# Power_Supply.net
KiCad netlist of a schematic drawn in Altium Designer
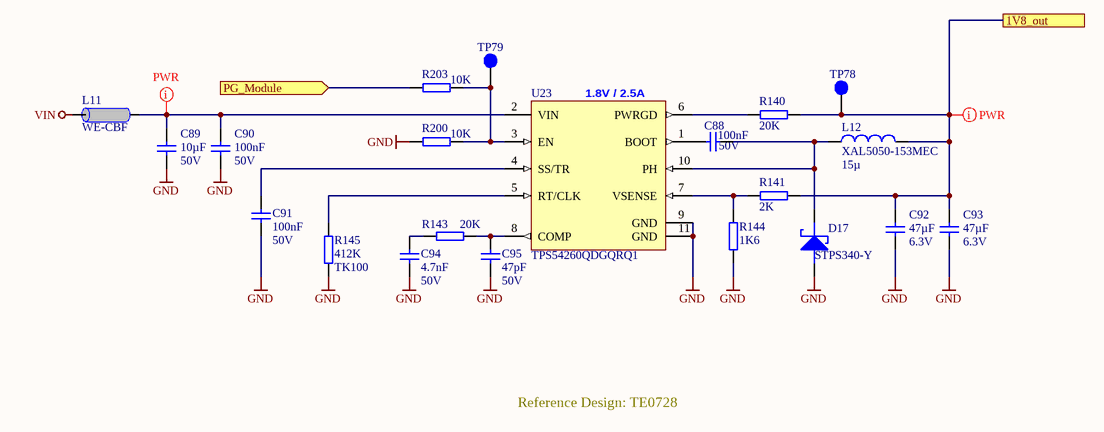
[diagram p0: Power_Supply.SchDoc]

(export (version "E")
  (design (tool "Eeschema 10.0.6"))
  (components
    (comp (ref "C88")
      (value "100nF")
      (footprint "CAPC1608X90N_FED")
      (description "KON 100nF 50V X7R ±10% SMD BF 1608 (0603)")
      (fields (field (name "TOLERANCE") "±10%") (field (name "VOLTAGE") "50V"))
      (libsource (lib "TE") (part "CAP-NP"))
    )
    (comp (ref "C89")
      (value "10µF")
      (footprint "CAPC3216X180N_V")
      (description "KON 10µF 50V X5R 10%  SMD BF 3216 (1206)")
      (fields (field (name "VOLTAGE") "50V") (field (name "TOLERANCE") "10%"))
      (libsource (lib "TE") (part "CAP-NP"))
    )
    (comp (ref "C90")
      (value "100nF")
      (footprint "CAPC1608X90N_FED")
      (description "KON 100nF 50V X7R ±10% SMD BF 1608 (0603)")
      (fields (field (name "TOLERANCE") "±10%") (field (name "VOLTAGE") "50V"))
      (libsource (lib "TE") (part "CAP-NP"))
    )
    (comp (ref "C91")
      (value "100nF")
      (footprint "CAPC1608X90N_FED")
      (description "KON 100nF 50V X7R ±10% SMD BF 1608 (0603)")
      (fields (field (name "TOLERANCE") "±10%") (field (name "VOLTAGE") "50V"))
      (libsource (lib "TE") (part "CAP-NP"))
    )
    (comp (ref "C92")
      (value "47µF")
      (footprint "CAPC2012X135N_V")
      (description "KON 47µF 6,3V X5R 20% SMD BF 2012 (0805)")
      (fields (field (name "TOLERANCE") "20%") (field (name "VOLTAGE") "6.3V"))
      (libsource (lib "TE") (part "CAP-NP"))
    )
    (comp (ref "C93")
      (value "47µF")
      (footprint "CAPC2012X135N_V")
      (description "KON 47µF 6,3V X5R 20% SMD BF 2012 (0805)")
      (fields (field (name "TOLERANCE") "20%") (field (name "VOLTAGE") "6.3V"))
      (libsource (lib "TE") (part "CAP-NP"))
    )
    (comp (ref "C94")
      (value "4.7nF")
      (footprint "CAPC1608X90N_FED")
      (description "KON 4.7nF 50V NP0 ±5%  SMD BF 1608 (0603)")
      (fields (field (name "TOLERANCE") "±5%") (field (name "VOLTAGE") "50V"))
      (libsource (lib "TE") (part "CAP-NP"))
    )
    (comp (ref "C95")
      (value "47pF")
      (footprint "CAPC1608X90N_FED")
      (description "KON 47pF 50V NP0 5%  SMD BF 1608 (0603)")
      (fields (field (name "TOLERANCE") "5%") (field (name "VOLTAGE") "50V"))
      (libsource (lib "TE") (part "CAP-NP"))
    )
    (comp (ref "D17")
      (value "STPS340-Y")
      (footprint "DIOM5336X265N")
      (description "STPS340-UY")
      (fields (field (name "VOLTAGE") "40V"))
      (libsource (lib "TE") (part "SCHOTTKY"))
    )
    (comp (ref "L11")
      (value "WE-CBF")
      (footprint "INDC2012X92N_V")
      (description "Ferritdurchführung SMD 0805")
      (fields (field (name "VOLTAGE") "2000mA"))
      (libsource (lib "TE") (part "Ferritperle"))
    )
    (comp (ref "L12")
      (value "XAL5050-153MEC")
      (footprint "IND_XAL5050")
      (description "Power Inductor 15µH 20% 3.9A 76.7mOhms")
      (fields (field (name "ALTIUM_VALUE") "15µ") (field (name "VOLTAGE") "3.9A 76.7mOhms"))
      (libsource (lib "TE") (part "IND"))
    )
    (comp (ref "R140")
      (value "20K")
      (footprint "RESC1608X55N_FED")
      (description "WID SMD 20K 1% 0,1W")
      (fields (field (name "TOLERANCE") "1%"))
      (libsource (lib "TE") (part "RES"))
    )
    (comp (ref "R141")
      (value "2K")
      (footprint "RESC1608X55N_FED")
      (description "WID SMD 2K 1% 0,1W AEC-Q200")
      (fields (field (name "TOLERANCE") "1%"))
      (libsource (lib "TE") (part "RES"))
    )
    (comp (ref "R143")
      (value "20K")
      (footprint "RESC1608X55N_FED")
      (description "WID SMD 20K 1% 0,1W")
      (fields (field (name "TOLERANCE") "1%"))
      (libsource (lib "TE") (part "RES"))
    )
    (comp (ref "R144")
      (value "1K6")
      (footprint "RESC1608X55N_FED")
      (description "WID SMD 1K6 1% 0,1W AEC-Q200")
      (fields (field (name "TOLERANCE") "1%"))
      (libsource (lib "TE") (part "RES"))
    )
    (comp (ref "R145")
      (value "412K")
      (footprint "RESC1608X55N_FED")
      (description "WID SMD 412K 1% 0,1W AEC-Q200")
      (fields (field (name "TOLERANCE") "1%") (field (name "TECHNOLOGY") "TK100"))
      (libsource (lib "TE") (part "RES"))
    )
    (comp (ref "R200")
      (value "10K")
      (footprint "RESC1608X55N_FED")
      (description "WID SMD 10K 1% 0,1W")
      (fields (field (name "TOLERANCE") "1%"))
      (libsource (lib "TE") (part "RES"))
    )
    (comp (ref "R203")
      (value "10K")
      (footprint "RESC1608X55N_FED")
      (description "WID SMD 10K 1% 0,1W")
      (fields (field (name "TOLERANCE") "1%"))
      (libsource (lib "TE") (part "RES"))
    )
    (comp (ref "TP78") (value "Testpoint 1mm") (footprint "TP_1mm") (libsource (lib "TE") (part "TP")))
    (comp (ref "TP79") (value "Testpoint 1mm") (footprint "TP_1mm") (libsource (lib "TE") (part "TP")))
    (comp (ref "U23")
      (value "TPS54260QDGQRQ1")
      (footprint "TSSOP50P490X110-11N-TI-DGQ")
      (libsource (lib "TE") (part "TPS54040A"))
    )
  )
  (nets
    (net (code "1") (name "/1V8_out") (class "Default")
      (node (ref "C92") (pin "2") (pinfunction "2_2") (pintype "passive"))
      (node (ref "C93") (pin "2") (pinfunction "2_2") (pintype "passive"))
      (node (ref "L12") (pin "2") (pinfunction "2_2") (pintype "passive"))
      (node (ref "R140") (pin "1") (pinfunction "1_1") (pintype "passive"))
      (node (ref "R141") (pin "1") (pinfunction "1_1") (pintype "passive"))
      (node (ref "TP78") (pin "1") (pintype "passive"))
    )
    (net (code "2") (name "/PG_Module") (class "Default")
      (node (ref "R203") (pin "1") (pinfunction "1_1") (pintype "passive"))
    )
    (net (code "3") (name "GND") (class "Default")
      (node (ref "C89") (pin "2") (pinfunction "2_2") (pintype "passive"))
      (node (ref "C90") (pin "1") (pinfunction "1_1") (pintype "passive"))
      (node (ref "C91") (pin "1") (pinfunction "1_1") (pintype "passive"))
      (node (ref "C92") (pin "1") (pinfunction "1_1") (pintype "passive"))
      (node (ref "C93") (pin "1") (pinfunction "1_1") (pintype "passive"))
      (node (ref "C94") (pin "2") (pinfunction "2_2") (pintype "passive"))
      (node (ref "C95") (pin "2") (pinfunction "2_2") (pintype "passive"))
      (node (ref "D17") (pin "2") (pinfunction "ANODE_2") (pintype "passive"))
      (node (ref "R144") (pin "2") (pinfunction "2_2") (pintype "passive"))
      (node (ref "R145") (pin "2") (pinfunction "2_2") (pintype "passive"))
      (node (ref "R200") (pin "1") (pinfunction "1_1") (pintype "passive"))
      (node (ref "U23") (pin "11") (pinfunction "GND_11") (pintype "power_in"))
      (node (ref "U23") (pin "9") (pinfunction "GND_9") (pintype "power_in"))
    )
    (net (code "4") (name "Net-(C94-Pad1)") (class "Default")
      (node (ref "C94") (pin "1") (pinfunction "1_1") (pintype "passive"))
      (node (ref "R143") (pin "2") (pinfunction "2_2") (pintype "passive"))
    )
    (net (code "5") (name "Net-(D17-KATHODE)") (class "Default")
      (node (ref "C88") (pin "1") (pinfunction "1_1") (pintype "passive"))
      (node (ref "D17") (pin "1") (pinfunction "KATHODE_1") (pintype "passive"))
      (node (ref "L12") (pin "1") (pinfunction "1_1") (pintype "passive"))
      (node (ref "U23") (pin "10") (pinfunction "PH_10") (pintype "input"))
    )
    (net (code "6") (name "Net-(U23-BOOT)") (class "Default")
      (node (ref "C88") (pin "2") (pinfunction "2_2") (pintype "passive"))
      (node (ref "U23") (pin "1") (pinfunction "BOOT_1") (pintype "output"))
    )
    (net (code "7") (name "Net-(U23-COMP)") (class "Default")
      (node (ref "C95") (pin "1") (pinfunction "1_1") (pintype "passive"))
      (node (ref "R143") (pin "1") (pinfunction "1_1") (pintype "passive"))
      (node (ref "U23") (pin "8") (pinfunction "COMP_8") (pintype "output"))
    )
    (net (code "8") (name "Net-(U23-EN)") (class "Default")
      (node (ref "R200") (pin "2") (pinfunction "2_2") (pintype "passive"))
      (node (ref "R203") (pin "2") (pinfunction "2_2") (pintype "passive"))
      (node (ref "TP79") (pin "1") (pintype "passive"))
      (node (ref "U23") (pin "3") (pinfunction "EN_3") (pintype "input"))
    )
    (net (code "9") (name "Net-(U23-PWRGD)") (class "Default")
      (node (ref "R140") (pin "2") (pinfunction "2_2") (pintype "passive"))
      (node (ref "U23") (pin "6") (pinfunction "PWRGD_6") (pintype "output"))
    )
    (net (code "10") (name "Net-(U23-RT{slash}CLK)") (class "Default")
      (node (ref "R145") (pin "1") (pinfunction "1_1") (pintype "passive"))
      (node (ref "U23") (pin "5") (pinfunction "RT/CLK_5") (pintype "input"))
    )
    (net (code "11") (name "Net-(U23-SS{slash}TR)") (class "Default")
      (node (ref "C91") (pin "2") (pinfunction "2_2") (pintype "passive"))
      (node (ref "U23") (pin "4") (pinfunction "SS/TR_4") (pintype "input"))
    )
    (net (code "12") (name "Net-(U23-VIN)") (class "Default")
      (node (ref "C89") (pin "1") (pinfunction "1_1") (pintype "passive"))
      (node (ref "C90") (pin "2") (pinfunction "2_2") (pintype "passive"))
      (node (ref "L11") (pin "1") (pinfunction "1_1") (pintype "passive"))
      (node (ref "U23") (pin "2") (pinfunction "VIN_2") (pintype "power_in"))
    )
    (net (code "13") (name "Net-(U23-VSENSE)") (class "Default")
      (node (ref "R141") (pin "2") (pinfunction "2_2") (pintype "passive"))
      (node (ref "R144") (pin "1") (pinfunction "1_1") (pintype "passive"))
      (node (ref "U23") (pin "7") (pinfunction "VSENSE_7") (pintype "input"))
    )
    (net (code "14") (name "VIN") (class "Default")
      (node (ref "L11") (pin "2") (pinfunction "2_2") (pintype "passive"))
    )
  )
)
